# FanControl.net
KiCad netlist of a schematic drawn in EAGLE
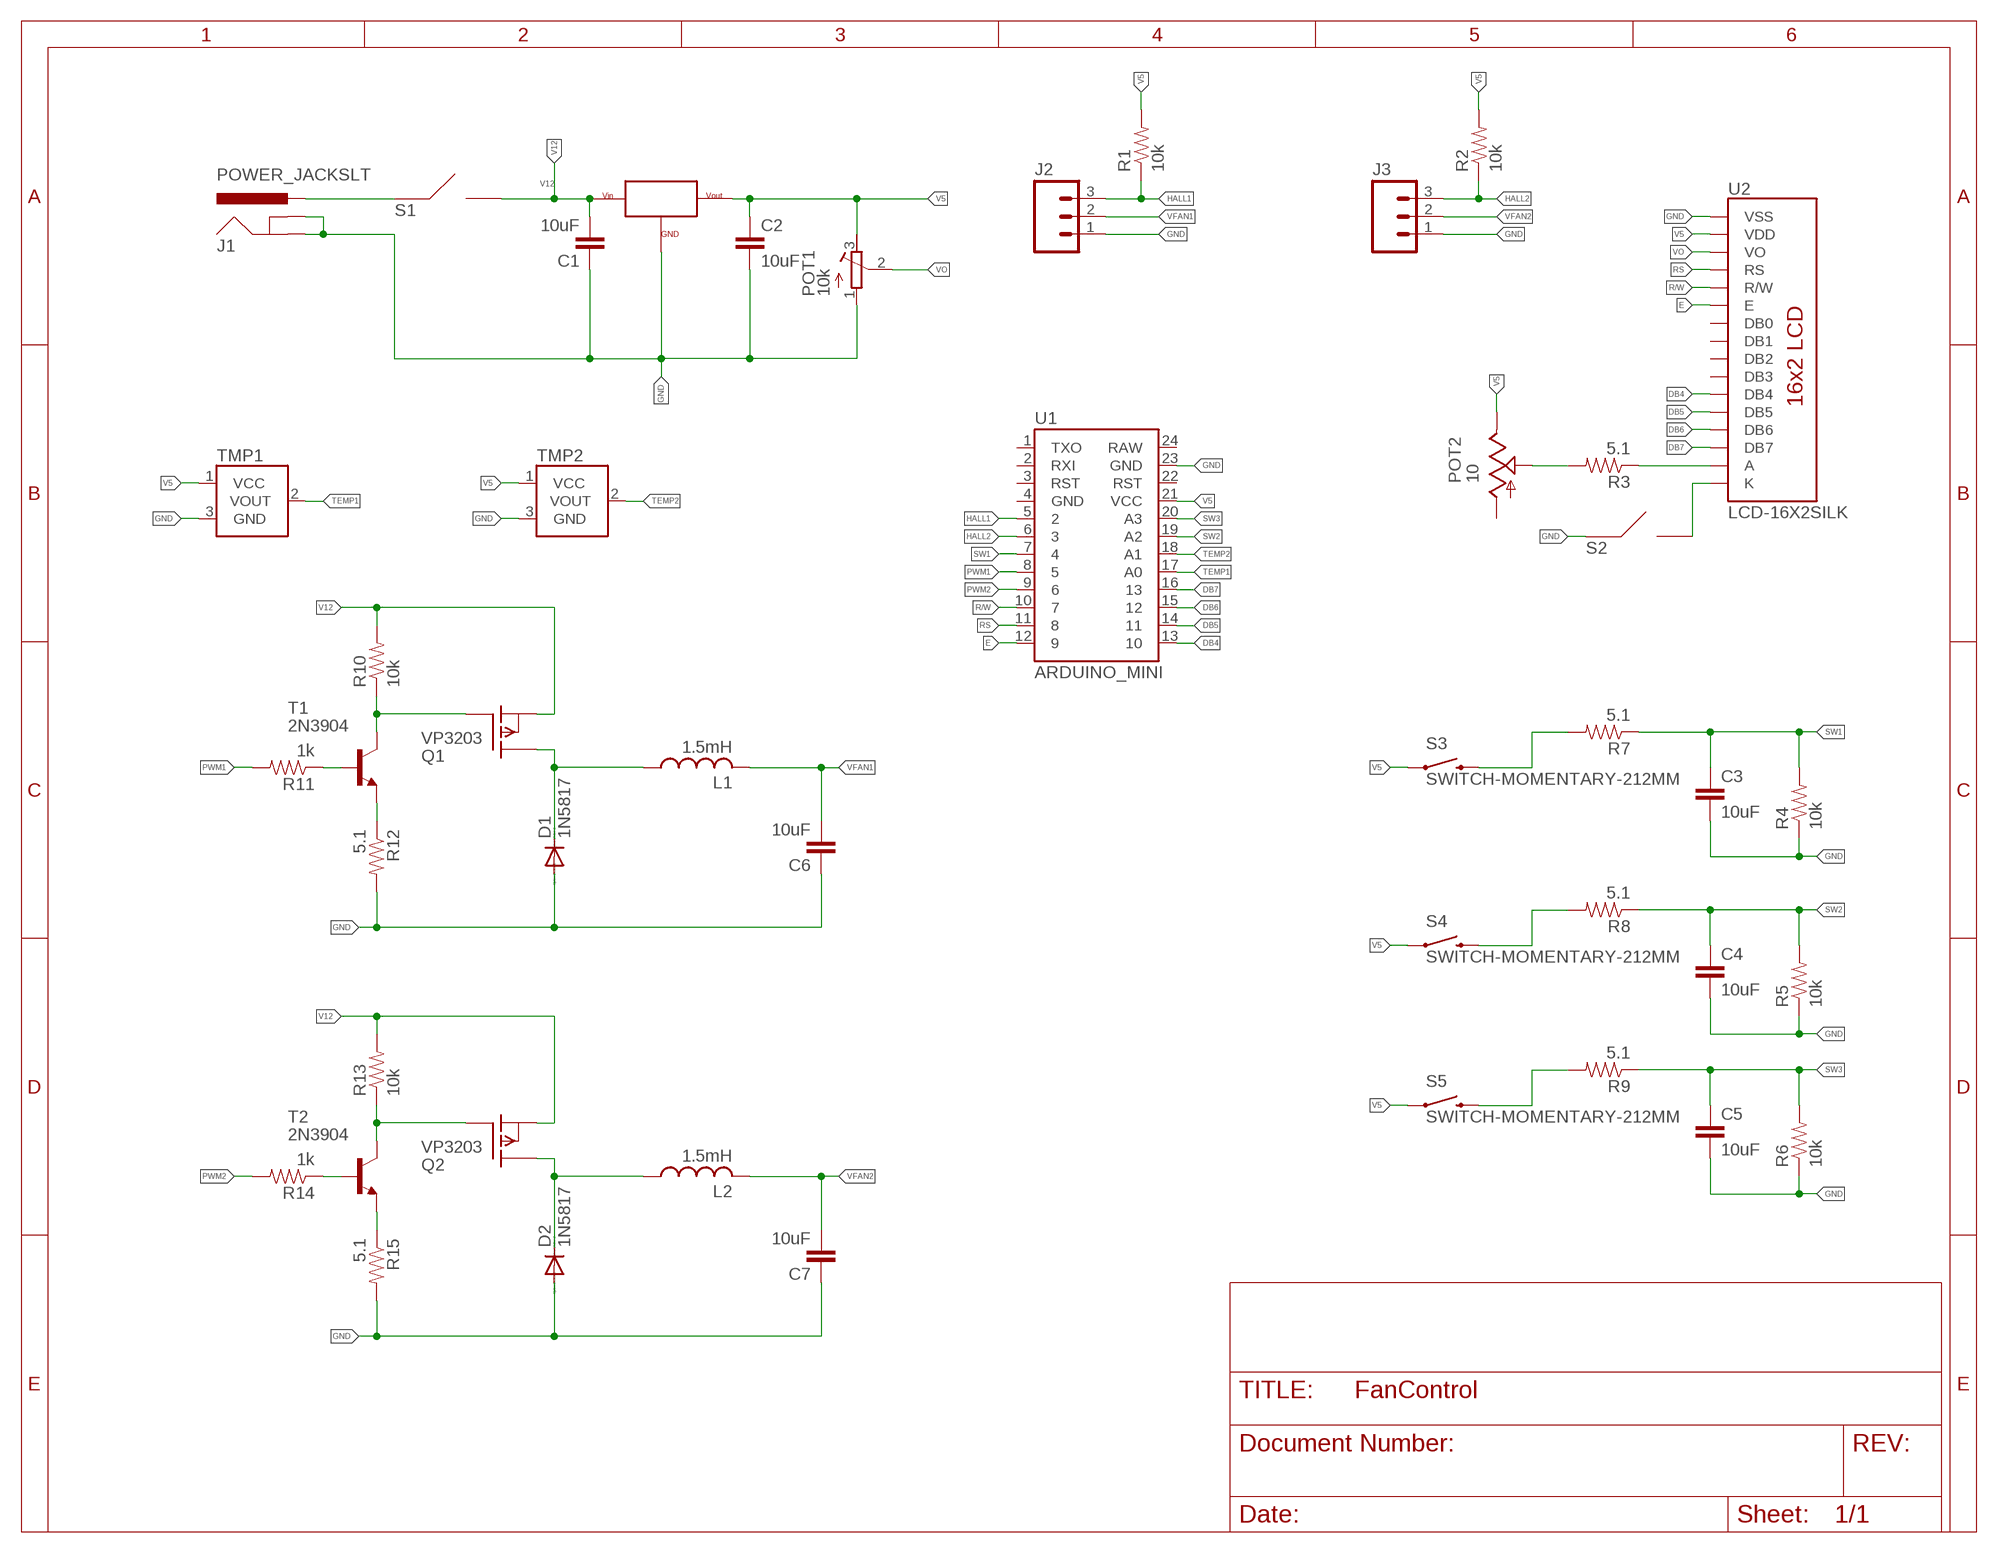
[diagram p0: schematic, sheet 1]

(export (version "E")
  (design (tool "Eeschema 10.0.6"))
  (components
    (comp (ref "C1")
      (value "10uF")
      (footprint "eagle-import:CAP-PTH-5MM")
      (libsource (lib "eagle-import") (part "CAPPTH1"))
    )
    (comp (ref "C2")
      (value "10uF")
      (footprint "eagle-import:CAP-PTH-5MM")
      (libsource (lib "eagle-import") (part "CAPPTH1"))
    )
    (comp (ref "C3")
      (value "10uF")
      (footprint "eagle-import:CAP-PTH-5MM")
      (libsource (lib "eagle-import") (part "CAPPTH1"))
    )
    (comp (ref "C4")
      (value "10uF")
      (footprint "eagle-import:CAP-PTH-5MM")
      (libsource (lib "eagle-import") (part "CAPPTH1"))
    )
    (comp (ref "C5")
      (value "10uF")
      (footprint "eagle-import:CAP-PTH-5MM")
      (libsource (lib "eagle-import") (part "CAPPTH1"))
    )
    (comp (ref "C6")
      (value "10uF")
      (footprint "eagle-import:CAP-PTH-5MM")
      (libsource (lib "eagle-import") (part "CAPPTH1"))
    )
    (comp (ref "C7")
      (value "10uF")
      (footprint "eagle-import:CAP-PTH-5MM")
      (libsource (lib "eagle-import") (part "CAPPTH1"))
    )
    (comp (ref "D1")
      (value "1N5817")
      (footprint "eagle-import:DO41-10")
      (libsource (lib "eagle-import") (part "UF4003"))
    )
    (comp (ref "D2")
      (value "1N5817")
      (footprint "eagle-import:DO41-10")
      (libsource (lib "eagle-import") (part "UF4003"))
    )
    (comp (ref "J1")
      (value "POWER_JACKSLT")
      (footprint "eagle-import:POWER_JACK_SLOT")
      (libsource (lib "eagle-import") (part "POWER_JACKSLT"))
    )
    (comp (ref "J2")
      (value "M03POLAR")
      (footprint "eagle-import:MOLEX-1X3")
      (libsource (lib "eagle-import") (part "M03POLAR"))
    )
    (comp (ref "J3")
      (value "M03POLAR")
      (footprint "eagle-import:MOLEX-1X3")
      (libsource (lib "eagle-import") (part "M03POLAR"))
    )
    (comp (ref "L1")
      (value "1.5mH")
      (footprint "eagle-import:0204_7")
      (libsource (lib "eagle-import") (part "L-US0204/7"))
    )
    (comp (ref "L2")
      (value "1.5mH")
      (footprint "eagle-import:0204_7")
      (libsource (lib "eagle-import") (part "L-US0204/7"))
    )
    (comp (ref "POT1")
      (value "10k")
      (footprint "eagle-import:RTRIM3362P")
      (libsource (lib "eagle-import") (part "RTRIM-3362P"))
    )
    (comp (ref "POT2")
      (value "10")
      (footprint "eagle-import:B25P")
      (libsource (lib "eagle-import") (part "TRIM_US-B25P"))
    )
    (comp (ref "Q1")
      (value "VP3203")
      (footprint "eagle-import:TO-92")
      (libsource (lib "eagle-import") (part "TP0602N3"))
    )
    (comp (ref "Q2")
      (value "VP3203")
      (footprint "eagle-import:TO-92")
      (libsource (lib "eagle-import") (part "TP0602N3"))
    )
    (comp (ref "R1")
      (value "10k")
      (footprint "eagle-import:1_6W-RES")
      (libsource (lib "eagle-import") (part "RESISTORPTH-1/6W"))
    )
    (comp (ref "R2")
      (value "10k")
      (footprint "eagle-import:1_6W-RES")
      (libsource (lib "eagle-import") (part "RESISTORPTH-1/6W"))
    )
    (comp (ref "R3")
      (value "5.1")
      (footprint "eagle-import:1_6W-RES")
      (libsource (lib "eagle-import") (part "RESISTORPTH-1/6W"))
    )
    (comp (ref "R4")
      (value "10k")
      (footprint "eagle-import:1_6W-RES")
      (libsource (lib "eagle-import") (part "RESISTORPTH-1/6W"))
    )
    (comp (ref "R5")
      (value "10k")
      (footprint "eagle-import:1_6W-RES")
      (libsource (lib "eagle-import") (part "RESISTORPTH-1/6W"))
    )
    (comp (ref "R6")
      (value "10k")
      (footprint "eagle-import:1_6W-RES")
      (libsource (lib "eagle-import") (part "RESISTORPTH-1/6W"))
    )
    (comp (ref "R7")
      (value "5.1")
      (footprint "eagle-import:1_6W-RES")
      (libsource (lib "eagle-import") (part "RESISTORPTH-1/6W"))
    )
    (comp (ref "R8")
      (value "5.1")
      (footprint "eagle-import:1_6W-RES")
      (libsource (lib "eagle-import") (part "RESISTORPTH-1/6W"))
    )
    (comp (ref "R9")
      (value "5.1")
      (footprint "eagle-import:1_6W-RES")
      (libsource (lib "eagle-import") (part "RESISTORPTH-1/6W"))
    )
    (comp (ref "R10")
      (value "10k")
      (footprint "eagle-import:1_6W-RES")
      (libsource (lib "eagle-import") (part "RESISTORPTH-1/6W"))
    )
    (comp (ref "R11")
      (value "1k")
      (footprint "eagle-import:1_6W-RES")
      (libsource (lib "eagle-import") (part "RESISTORPTH-1/6W"))
    )
    (comp (ref "R12")
      (value "5.1")
      (footprint "eagle-import:1_6W-RES")
      (libsource (lib "eagle-import") (part "RESISTORPTH-1/6W"))
    )
    (comp (ref "R13")
      (value "10k")
      (footprint "eagle-import:1_6W-RES")
      (libsource (lib "eagle-import") (part "RESISTORPTH-1/6W"))
    )
    (comp (ref "R14")
      (value "1k")
      (footprint "eagle-import:1_6W-RES")
      (libsource (lib "eagle-import") (part "RESISTORPTH-1/6W"))
    )
    (comp (ref "R15")
      (value "5.1")
      (footprint "eagle-import:1_6W-RES")
      (libsource (lib "eagle-import") (part "RESISTORPTH-1/6W"))
    )
    (comp (ref "S1")
      (value "SLIDE_SWITCH")
      (footprint "eagle-import:TH_SLIDE_SWITCH")
      (libsource (lib "eagle-import") (part "SLIDE_SWITCH"))
    )
    (comp (ref "S2")
      (value "SLIDE_SWITCH")
      (footprint "eagle-import:TH_SLIDE_SWITCH")
      (libsource (lib "eagle-import") (part "SLIDE_SWITCH"))
    )
    (comp (ref "S3")
      (value "SWITCH-MOMENTARY-212MM")
      (footprint "eagle-import:TACTILE-PTH-12MM")
      (libsource (lib "eagle-import") (part "SWITCH-MOMENTARY-212MM"))
    )
    (comp (ref "S4")
      (value "SWITCH-MOMENTARY-212MM")
      (footprint "eagle-import:TACTILE-PTH-12MM")
      (libsource (lib "eagle-import") (part "SWITCH-MOMENTARY-212MM"))
    )
    (comp (ref "S5")
      (value "SWITCH-MOMENTARY-212MM")
      (footprint "eagle-import:TACTILE-PTH-12MM")
      (libsource (lib "eagle-import") (part "SWITCH-MOMENTARY-212MM"))
    )
    (comp (ref "T1")
      (value "2N3904")
      (footprint "eagle-import:TO92")
      (libsource (lib "eagle-import") (part "2N3904"))
    )
    (comp (ref "T2")
      (value "2N3904")
      (footprint "eagle-import:TO92")
      (libsource (lib "eagle-import") (part "2N3904"))
    )
    (comp (ref "TMP1")
      (value "TMP36GT9")
      (footprint "eagle-import:TO-92")
      (libsource (lib "eagle-import") (part "TMP36GT9"))
    )
    (comp (ref "TMP2")
      (value "TMP36GT9")
      (footprint "eagle-import:TO-92")
      (libsource (lib "eagle-import") (part "TMP36GT9"))
    )
    (comp (ref "U$1")
      (value "R-78EXX-0.5")
      (footprint "eagle-import:R-78EXX-0.5")
      (libsource (lib "eagle-import") (part "R-78EXX-0.5"))
    )
    (comp (ref "U1")
      (value "ARDUINO_MINI")
      (footprint "eagle-import:ARDUINO_MINI")
      (libsource (lib "eagle-import") (part "ARDUINO_MINI"))
    )
    (comp (ref "U2")
      (value "LCD-16X2SILK")
      (footprint "eagle-import:LCD-16X2")
      (libsource (lib "eagle-import") (part "LCD-16X2SILK"))
    )
  )
  (nets
    (net (code "1") (name "DB4") (class "Default")
      (node (ref "U1") (pin "13") (pinfunction "10_13") (pintype "bidirectional"))
      (node (ref "U2") (pin "11") (pinfunction "DB4_11") (pintype "bidirectional"))
    )
    (net (code "2") (name "DB5") (class "Default")
      (node (ref "U1") (pin "14") (pinfunction "11_14") (pintype "bidirectional"))
      (node (ref "U2") (pin "12") (pinfunction "DB5_12") (pintype "bidirectional"))
    )
    (net (code "3") (name "DB6") (class "Default")
      (node (ref "U1") (pin "15") (pinfunction "12_15") (pintype "bidirectional"))
      (node (ref "U2") (pin "13") (pinfunction "DB6_13") (pintype "bidirectional"))
    )
    (net (code "4") (name "DB7") (class "Default")
      (node (ref "U1") (pin "16") (pinfunction "13_16") (pintype "bidirectional"))
      (node (ref "U2") (pin "14") (pinfunction "DB7_14") (pintype "bidirectional"))
    )
    (net (code "5") (name "E") (class "Default")
      (node (ref "U1") (pin "12") (pinfunction "9_12") (pintype "bidirectional"))
      (node (ref "U2") (pin "6") (pinfunction "E_6") (pintype "input"))
    )
    (net (code "6") (name "GND") (class "Default")
      (node (ref "C1") (pin "1") (pinfunction "1_1") (pintype "passive"))
      (node (ref "C2") (pin "2") (pinfunction "2_2") (pintype "passive"))
      (node (ref "C3") (pin "2") (pinfunction "2_2") (pintype "passive"))
      (node (ref "C4") (pin "2") (pinfunction "2_2") (pintype "passive"))
      (node (ref "C5") (pin "2") (pinfunction "2_2") (pintype "passive"))
      (node (ref "C6") (pin "1") (pinfunction "1_1") (pintype "passive"))
      (node (ref "C7") (pin "1") (pinfunction "1_1") (pintype "passive"))
      (node (ref "D1") (pin "A") (pinfunction "A_A") (pintype "passive"))
      (node (ref "D2") (pin "A") (pinfunction "A_A") (pintype "passive"))
      (node (ref "J1") (pin "GND@1") (pinfunction "GNDBREAK_GND@1") (pintype "bidirectional"))
      (node (ref "J1") (pin "GND@2") (pinfunction "GND_GND@2") (pintype "bidirectional"))
      (node (ref "J2") (pin "1") (pinfunction "1_1") (pintype "passive"))
      (node (ref "J3") (pin "1") (pinfunction "1_1") (pintype "passive"))
      (node (ref "POT1") (pin "1") (pinfunction "1_1") (pintype "passive"))
      (node (ref "R12") (pin "2") (pinfunction "2_2") (pintype "passive"))
      (node (ref "R15") (pin "2") (pinfunction "2_2") (pintype "passive"))
      (node (ref "R4") (pin "1") (pinfunction "1_1") (pintype "passive"))
      (node (ref "R5") (pin "1") (pinfunction "1_1") (pintype "passive"))
      (node (ref "R6") (pin "1") (pinfunction "1_1") (pintype "passive"))
      (node (ref "S2") (pin "A") (pinfunction "A_A") (pintype "bidirectional"))
      (node (ref "TMP1") (pin "3") (pinfunction "GND_3") (pintype "bidirectional"))
      (node (ref "TMP2") (pin "3") (pinfunction "GND_3") (pintype "bidirectional"))
      (node (ref "U$1") (pin "GND") (pinfunction "GND_GND") (pintype "bidirectional"))
      (node (ref "U1") (pin "23") (pinfunction "GND_23") (pintype "bidirectional"))
      (node (ref "U2") (pin "1") (pinfunction "VSS_1") (pintype "power_in"))
    )
    (net (code "7") (name "HALL1") (class "Default")
      (node (ref "J2") (pin "3") (pinfunction "3_3") (pintype "passive"))
      (node (ref "R1") (pin "1") (pinfunction "1_1") (pintype "passive"))
      (node (ref "U1") (pin "5") (pinfunction "2_5") (pintype "bidirectional"))
    )
    (net (code "8") (name "HALL2") (class "Default")
      (node (ref "J3") (pin "3") (pinfunction "3_3") (pintype "passive"))
      (node (ref "R2") (pin "1") (pinfunction "1_1") (pintype "passive"))
      (node (ref "U1") (pin "6") (pinfunction "3_6") (pintype "bidirectional"))
    )
    (net (code "9") (name "Net-(J1-PadPWR)") (class "Default")
      (node (ref "J1") (pin "PWR") (pinfunction "PWR_PWR") (pintype "bidirectional"))
      (node (ref "S1") (pin "A") (pinfunction "A_A") (pintype "bidirectional"))
    )
    (net (code "10") (name "Net-(POT2-PadS)") (class "Default")
      (node (ref "POT2") (pin "S") (pinfunction "S_S") (pintype "passive"))
      (node (ref "R3") (pin "2") (pinfunction "2_2") (pintype "passive"))
    )
    (net (code "11") (name "Net-(Q1-D)") (class "Default")
      (node (ref "D1") (pin "C") (pinfunction "C_C") (pintype "passive"))
      (node (ref "L1") (pin "1") (pinfunction "1_1") (pintype "passive"))
      (node (ref "Q1") (pin "3") (pinfunction "D_3") (pintype "passive"))
    )
    (net (code "12") (name "Net-(Q1-G)") (class "Default")
      (node (ref "Q1") (pin "2") (pinfunction "G_2") (pintype "passive"))
      (node (ref "R10") (pin "1") (pinfunction "1_1") (pintype "passive"))
      (node (ref "T1") (pin "1") (pinfunction "C_1") (pintype "passive"))
    )
    (net (code "13") (name "Net-(Q2-D)") (class "Default")
      (node (ref "D2") (pin "C") (pinfunction "C_C") (pintype "passive"))
      (node (ref "L2") (pin "1") (pinfunction "1_1") (pintype "passive"))
      (node (ref "Q2") (pin "3") (pinfunction "D_3") (pintype "passive"))
    )
    (net (code "14") (name "Net-(Q2-G)") (class "Default")
      (node (ref "Q2") (pin "2") (pinfunction "G_2") (pintype "passive"))
      (node (ref "R13") (pin "1") (pinfunction "1_1") (pintype "passive"))
      (node (ref "T2") (pin "1") (pinfunction "C_1") (pintype "passive"))
    )
    (net (code "15") (name "Net-(S3-2)") (class "Default")
      (node (ref "R7") (pin "2") (pinfunction "2_2") (pintype "passive"))
      (node (ref "S3") (pin "3") (pinfunction "2_3") (pintype "passive"))
    )
    (net (code "16") (name "Net-(S4-2)") (class "Default")
      (node (ref "R8") (pin "2") (pinfunction "2_2") (pintype "passive"))
      (node (ref "S4") (pin "3") (pinfunction "2_3") (pintype "passive"))
    )
    (net (code "17") (name "Net-(S5-2)") (class "Default")
      (node (ref "R9") (pin "2") (pinfunction "2_2") (pintype "passive"))
      (node (ref "S5") (pin "3") (pinfunction "2_3") (pintype "passive"))
    )
    (net (code "18") (name "Net-(T1-B)") (class "Default")
      (node (ref "R11") (pin "1") (pinfunction "1_1") (pintype "passive"))
      (node (ref "T1") (pin "2") (pinfunction "B_2") (pintype "passive"))
    )
    (net (code "19") (name "Net-(T1-E)") (class "Default")
      (node (ref "R12") (pin "1") (pinfunction "1_1") (pintype "passive"))
      (node (ref "T1") (pin "3") (pinfunction "E_3") (pintype "passive"))
    )
    (net (code "20") (name "Net-(T2-B)") (class "Default")
      (node (ref "R14") (pin "1") (pinfunction "1_1") (pintype "passive"))
      (node (ref "T2") (pin "2") (pinfunction "B_2") (pintype "passive"))
    )
    (net (code "21") (name "Net-(T2-E)") (class "Default")
      (node (ref "R15") (pin "1") (pinfunction "1_1") (pintype "passive"))
      (node (ref "T2") (pin "3") (pinfunction "E_3") (pintype "passive"))
    )
    (net (code "22") (name "Net-(U2-A)") (class "Default")
      (node (ref "R3") (pin "1") (pinfunction "1_1") (pintype "passive"))
      (node (ref "U2") (pin "15") (pinfunction "A_15") (pintype "power_in"))
    )
    (net (code "23") (name "Net-(U2-K)") (class "Default")
      (node (ref "S2") (pin "B") (pinfunction "B_B") (pintype "bidirectional"))
      (node (ref "U2") (pin "16") (pinfunction "K_16") (pintype "power_in"))
    )
    (net (code "24") (name "PWM1") (class "Default")
      (node (ref "R11") (pin "2") (pinfunction "2_2") (pintype "passive"))
      (node (ref "U1") (pin "8") (pinfunction "5_8") (pintype "bidirectional"))
    )
    (net (code "25") (name "PWM2") (class "Default")
      (node (ref "R14") (pin "2") (pinfunction "2_2") (pintype "passive"))
      (node (ref "U1") (pin "9") (pinfunction "6_9") (pintype "bidirectional"))
    )
    (net (code "26") (name "RS") (class "Default")
      (node (ref "U1") (pin "11") (pinfunction "8_11") (pintype "bidirectional"))
      (node (ref "U2") (pin "4") (pinfunction "RS_4") (pintype "input"))
    )
    (net (code "27") (name "R{slash}W") (class "Default")
      (node (ref "U1") (pin "10") (pinfunction "7_10") (pintype "bidirectional"))
      (node (ref "U2") (pin "5") (pinfunction "R/W_5") (pintype "input"))
    )
    (net (code "28") (name "SW1") (class "Default")
      (node (ref "C3") (pin "1") (pinfunction "1_1") (pintype "passive"))
      (node (ref "R4") (pin "2") (pinfunction "2_2") (pintype "passive"))
      (node (ref "R7") (pin "1") (pinfunction "1_1") (pintype "passive"))
      (node (ref "U1") (pin "7") (pinfunction "4_7") (pintype "bidirectional"))
    )
    (net (code "29") (name "SW2") (class "Default")
      (node (ref "C4") (pin "1") (pinfunction "1_1") (pintype "passive"))
      (node (ref "R5") (pin "2") (pinfunction "2_2") (pintype "passive"))
      (node (ref "R8") (pin "1") (pinfunction "1_1") (pintype "passive"))
      (node (ref "U1") (pin "19") (pinfunction "A2_19") (pintype "bidirectional"))
    )
    (net (code "30") (name "SW3") (class "Default")
      (node (ref "C5") (pin "1") (pinfunction "1_1") (pintype "passive"))
      (node (ref "R6") (pin "2") (pinfunction "2_2") (pintype "passive"))
      (node (ref "R9") (pin "1") (pinfunction "1_1") (pintype "passive"))
      (node (ref "U1") (pin "20") (pinfunction "A3_20") (pintype "bidirectional"))
    )
    (net (code "31") (name "TEMP1") (class "Default")
      (node (ref "TMP1") (pin "2") (pinfunction "VOUT_2") (pintype "bidirectional"))
      (node (ref "U1") (pin "17") (pinfunction "A0_17") (pintype "bidirectional"))
    )
    (net (code "32") (name "TEMP2") (class "Default")
      (node (ref "TMP2") (pin "2") (pinfunction "VOUT_2") (pintype "bidirectional"))
      (node (ref "U1") (pin "18") (pinfunction "A1_18") (pintype "bidirectional"))
    )
    (net (code "33") (name "V5") (class "Default")
      (node (ref "C2") (pin "1") (pinfunction "1_1") (pintype "passive"))
      (node (ref "POT1") (pin "3") (pinfunction "3_3") (pintype "passive"))
      (node (ref "POT2") (pin "E") (pinfunction "E_E") (pintype "passive"))
      (node (ref "R1") (pin "2") (pinfunction "2_2") (pintype "passive"))
      (node (ref "R2") (pin "2") (pinfunction "2_2") (pintype "passive"))
      (node (ref "S3") (pin "1") (pinfunction "1_1") (pintype "passive"))
      (node (ref "S4") (pin "1") (pinfunction "1_1") (pintype "passive"))
      (node (ref "S5") (pin "1") (pinfunction "1_1") (pintype "passive"))
      (node (ref "TMP1") (pin "1") (pinfunction "VCC_1") (pintype "bidirectional"))
      (node (ref "TMP2") (pin "1") (pinfunction "VCC_1") (pintype "bidirectional"))
      (node (ref "U$1") (pin "VOUT") (pinfunction "VOUT_VOUT") (pintype "output"))
      (node (ref "U1") (pin "21") (pinfunction "VCC_21") (pintype "bidirectional"))
      (node (ref "U2") (pin "2") (pinfunction "VDD_2") (pintype "power_in"))
    )
    (net (code "34") (name "V12") (class "Default")
      (node (ref "C1") (pin "2") (pinfunction "2_2") (pintype "passive"))
      (node (ref "Q1") (pin "1") (pinfunction "S_1") (pintype "passive"))
      (node (ref "Q2") (pin "1") (pinfunction "S_1") (pintype "passive"))
      (node (ref "R10") (pin "2") (pinfunction "2_2") (pintype "passive"))
      (node (ref "R13") (pin "2") (pinfunction "2_2") (pintype "passive"))
      (node (ref "S1") (pin "B") (pinfunction "B_B") (pintype "bidirectional"))
      (node (ref "U$1") (pin "VIN") (pinfunction "VIN_VIN") (pintype "input"))
    )
    (net (code "35") (name "VFAN1") (class "Default")
      (node (ref "C6") (pin "2") (pinfunction "2_2") (pintype "passive"))
      (node (ref "J2") (pin "2") (pinfunction "2_2") (pintype "passive"))
      (node (ref "L1") (pin "2") (pinfunction "2_2") (pintype "passive"))
    )
    (net (code "36") (name "VFAN2") (class "Default")
      (node (ref "C7") (pin "2") (pinfunction "2_2") (pintype "passive"))
      (node (ref "J3") (pin "2") (pinfunction "2_2") (pintype "passive"))
      (node (ref "L2") (pin "2") (pinfunction "2_2") (pintype "passive"))
    )
    (net (code "37") (name "VO") (class "Default")
      (node (ref "POT1") (pin "2") (pinfunction "2_2") (pintype "passive"))
      (node (ref "U2") (pin "3") (pinfunction "VO_3") (pintype "bidirectional"))
    )
    (net (code "38") (name "unconnected-(POT2-PadA)") (class "Default")
      (node (ref "POT2") (pin "A") (pinfunction "A_A") (pintype "passive"))
    )
    (net (code "39") (name "unconnected-(U1-GND-Pad4)") (class "Default")
      (node (ref "U1") (pin "4") (pinfunction "GND_4") (pintype "bidirectional"))
    )
    (net (code "40") (name "unconnected-(U1-RAW-Pad24)") (class "Default")
      (node (ref "U1") (pin "24") (pinfunction "RAW_24") (pintype "bidirectional"))
    )
    (net (code "41") (name "unconnected-(U1-RST-Pad3)") (class "Default")
      (node (ref "U1") (pin "3") (pinfunction "RST_3") (pintype "bidirectional"))
    )
    (net (code "42") (name "unconnected-(U1-RST-Pad22)") (class "Default")
      (node (ref "U1") (pin "22") (pinfunction "RST_22") (pintype "bidirectional"))
    )
    (net (code "43") (name "unconnected-(U1-RXI-Pad2)") (class "Default")
      (node (ref "U1") (pin "2") (pinfunction "RXI_2") (pintype "bidirectional"))
    )
    (net (code "44") (name "unconnected-(U1-TXO-Pad1)") (class "Default")
      (node (ref "U1") (pin "1") (pinfunction "TXO_1") (pintype "bidirectional"))
    )
    (net (code "45") (name "unconnected-(U2-DB0-Pad7)") (class "Default")
      (node (ref "U2") (pin "7") (pinfunction "DB0_7") (pintype "bidirectional"))
    )
    (net (code "46") (name "unconnected-(U2-DB1-Pad8)") (class "Default")
      (node (ref "U2") (pin "8") (pinfunction "DB1_8") (pintype "bidirectional"))
    )
    (net (code "47") (name "unconnected-(U2-DB2-Pad9)") (class "Default")
      (node (ref "U2") (pin "9") (pinfunction "DB2_9") (pintype "bidirectional"))
    )
    (net (code "48") (name "unconnected-(U2-DB3-Pad10)") (class "Default")
      (node (ref "U2") (pin "10") (pinfunction "DB3_10") (pintype "bidirectional"))
    )
  )
)
